# CPU.net
KiCad netlist of a schematic drawn in Altium Designer
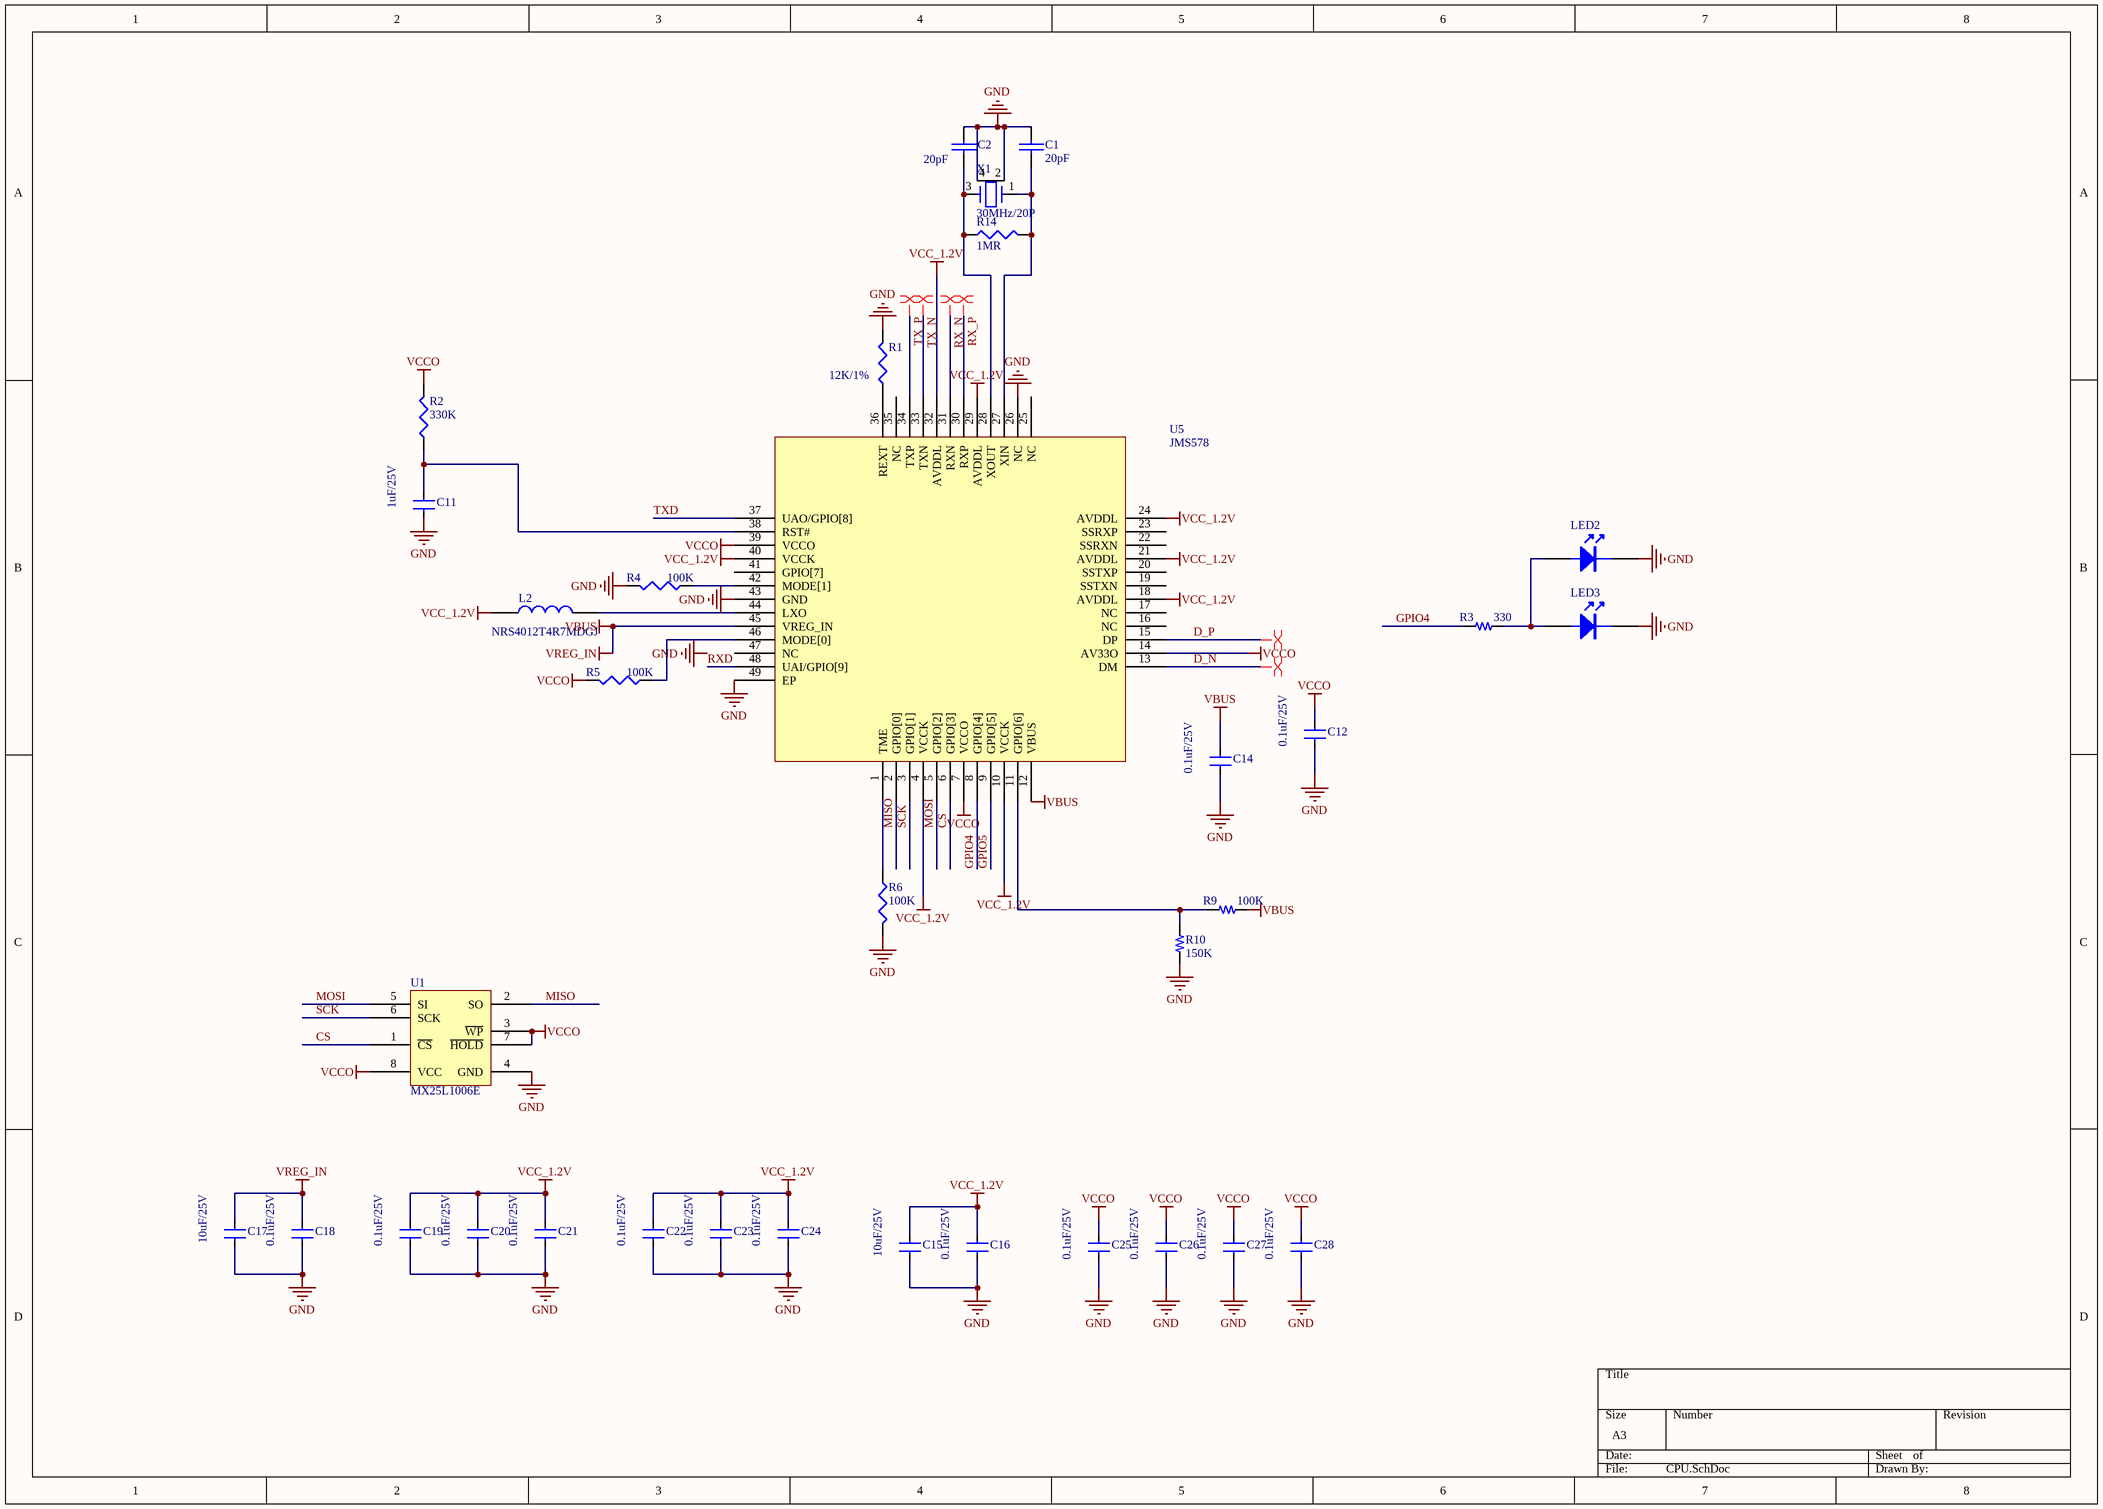
[diagram p0: CPU.SchDoc]

(export (version "E")
  (design (tool "Eeschema 10.0.6"))
  (components
    (comp (ref "C1")
      (value "20pF")
      (footprint "0603c")
      (description "Capacitor")
      (libsource (lib "SM") (part "CAP"))
    )
    (comp (ref "C2")
      (value "20pF")
      (footprint "0603C")
      (description "Capacitor")
      (libsource (lib "SM") (part "CAP"))
    )
    (comp (ref "C11")
      (value "1uF/25V")
      (footprint "0603C")
      (description "CCX85-103")
      (libsource (lib "无极性电容") (part "0.01UF"))
    )
    (comp (ref "C12")
      (value "0.1uF/25V")
      (footprint "0603C")
      (description "CCX85-103")
      (libsource (lib "无极性电容") (part "0.01UF"))
    )
    (comp (ref "C14")
      (value "0.1uF/25V")
      (footprint "0603C")
      (description "CCX85-103")
      (libsource (lib "无极性电容") (part "0.01UF"))
    )
    (comp (ref "C15")
      (value "10uF/25V")
      (footprint "0603C")
      (description "CCX85-103")
      (libsource (lib "无极性电容") (part "0.01UF"))
    )
    (comp (ref "C16")
      (value "0.1uF/25V")
      (footprint "0603C")
      (description "CCX85-103")
      (libsource (lib "无极性电容") (part "0.01UF"))
    )
    (comp (ref "C17")
      (value "10uF/25V")
      (footprint "0603C")
      (description "CCX85-103")
      (libsource (lib "无极性电容") (part "0.01UF"))
    )
    (comp (ref "C18")
      (value "0.1uF/25V")
      (footprint "0603C")
      (description "CCX85-103")
      (libsource (lib "无极性电容") (part "0.01UF"))
    )
    (comp (ref "C19")
      (value "0.1uF/25V")
      (footprint "0603C")
      (description "CCX85-103")
      (libsource (lib "无极性电容") (part "0.01UF"))
    )
    (comp (ref "C20")
      (value "0.1uF/25V")
      (footprint "0603C")
      (description "CCX85-103")
      (libsource (lib "无极性电容") (part "0.01UF"))
    )
    (comp (ref "C21")
      (value "0.1uF/25V")
      (footprint "0603C")
      (description "CCX85-103")
      (libsource (lib "无极性电容") (part "0.01UF"))
    )
    (comp (ref "C22")
      (value "0.1uF/25V")
      (footprint "0603C")
      (description "CCX85-103")
      (libsource (lib "无极性电容") (part "0.01UF"))
    )
    (comp (ref "C23")
      (value "0.1uF/25V")
      (footprint "0603C")
      (description "CCX85-103")
      (libsource (lib "无极性电容") (part "0.01UF"))
    )
    (comp (ref "C24")
      (value "0.1uF/25V")
      (footprint "0603C")
      (description "CCX85-103")
      (libsource (lib "无极性电容") (part "0.01UF"))
    )
    (comp (ref "C25")
      (value "0.1uF/25V")
      (footprint "0603C")
      (description "CCX85-103")
      (libsource (lib "无极性电容") (part "0.01UF"))
    )
    (comp (ref "C26")
      (value "0.1uF/25V")
      (footprint "0603C")
      (description "CCX85-103")
      (libsource (lib "无极性电容") (part "0.01UF"))
    )
    (comp (ref "C27")
      (value "0.1uF/25V")
      (footprint "0603C")
      (description "CCX85-103")
      (libsource (lib "无极性电容") (part "0.01UF"))
    )
    (comp (ref "C28")
      (value "0.1uF/25V")
      (footprint "0603C")
      (description "CCX85-103")
      (libsource (lib "无极性电容") (part "0.01UF"))
    )
    (comp (ref "L2")
      (value "NRS4012T4R7MDGJ")
      (footprint "NRS4012T4R7MDGJ")
      (libsource (lib "*") (part "INDUCTOR"))
    )
    (comp (ref "LED2") (value "~") (footprint "0603LED") (libsource (lib "*") (part "LED")))
    (comp (ref "LED3") (value "~") (footprint "0603LED") (libsource (lib "*") (part "LED")))
    (comp (ref "R1")
      (value "12K/1%")
      (footprint "0603R")
      (description "Resistor")
      (fields (field (name "PUBLISHER") "Altium Limited"))
      (libsource (lib "SM") (part "Res3"))
    )
    (comp (ref "R2")
      (value "330K")
      (footprint "0603R")
      (description "Resistor")
      (fields (field (name "PUBLISHER") "Altium Limited"))
      (libsource (lib "SM") (part "Res3"))
    )
    (comp (ref "R3") (value "330") (footprint "0603R") (description "R") (libsource (lib "JRJ_1") (part "R")))
    (comp (ref "R4")
      (value "100K")
      (footprint "0603R")
      (description "Resistor")
      (fields (field (name "PUBLISHER") "Altium Limited"))
      (libsource (lib "SM") (part "Res3"))
    )
    (comp (ref "R5")
      (value "100K")
      (footprint "0603R")
      (description "Resistor")
      (fields (field (name "PUBLISHER") "Altium Limited"))
      (libsource (lib "SM") (part "Res3"))
    )
    (comp (ref "R6")
      (value "100K")
      (footprint "0603R")
      (description "Resistor")
      (fields (field (name "PUBLISHER") "Altium Limited"))
      (libsource (lib "SM") (part "Res3"))
    )
    (comp (ref "R9")
      (value "100K")
      (footprint "0603R")
      (description "R")
      (libsource (lib "JRJ_1") (part "R"))
    )
    (comp (ref "R10")
      (value "150K")
      (footprint "0603R")
      (description "R")
      (libsource (lib "JRJ_1") (part "R"))
    )
    (comp (ref "R14")
      (value "1MR")
      (footprint "0603R")
      (description "Resistor")
      (fields (field (name "PUBLISHER") "Altium Limited"))
      (libsource (lib "SM") (part "Res3"))
    )
    (comp (ref "U1")
      (value "MX25L1006E")
      (footprint "SO-8")
      (libsource (lib "Schlib_20110825") (part "M25P40-VMN6"))
    )
    (comp (ref "U5") (value "JMS578") (footprint "QFN400P600-8N") (libsource (lib "stm32") (part "JMS578")))
    (comp (ref "X1")
      (value "30MHz/20P")
      (footprint "XTAL4TN_3225")
      (libsource (lib "JRJ") (part "CRYSTAL_2"))
    )
  )
  (nets
    (net (code "1") (name "/CS") (class "Default")
      (node (ref "U1") (pin "1") (pinfunction "~{CS}_1") (pintype "passive"))
      (node (ref "U5") (pin "6") (pinfunction "GPIO[3]_6") (pintype "passive"))
    )
    (net (code "2") (name "/D_N") (class "Default")
      (node (ref "U5") (pin "13") (pinfunction "DM_13") (pintype "passive"))
    )
    (net (code "3") (name "/D_P") (class "Default")
      (node (ref "U5") (pin "15") (pinfunction "DP_15") (pintype "passive"))
    )
    (net (code "4") (name "/GPIO4") (class "Default")
      (node (ref "R3") (pin "1") (pintype "passive"))
      (node (ref "U5") (pin "8") (pinfunction "GPIO[4]_8") (pintype "passive"))
    )
    (net (code "5") (name "/GPIO5") (class "Default")
      (node (ref "U5") (pin "9") (pinfunction "GPIO[5]_9") (pintype "passive"))
    )
    (net (code "6") (name "/MISO") (class "Default")
      (node (ref "U1") (pin "2") (pinfunction "SO_2") (pintype "passive"))
      (node (ref "U5") (pin "2") (pinfunction "GPIO[0]_2") (pintype "passive"))
    )
    (net (code "7") (name "/MOSI") (class "Default")
      (node (ref "U1") (pin "5") (pinfunction "SI_5") (pintype "passive"))
      (node (ref "U5") (pin "5") (pinfunction "GPIO[2]_5") (pintype "passive"))
    )
    (net (code "8") (name "/RXD") (class "Default")
      (node (ref "U5") (pin "48") (pinfunction "UAI/GPIO[9]_48") (pintype "passive"))
    )
    (net (code "9") (name "/RX_N") (class "Default")
      (node (ref "U5") (pin "31") (pinfunction "RXN_31") (pintype "passive"))
    )
    (net (code "10") (name "/RX_P") (class "Default")
      (node (ref "U5") (pin "30") (pinfunction "RXP_30") (pintype "passive"))
    )
    (net (code "11") (name "/SCK") (class "Default")
      (node (ref "U1") (pin "6") (pinfunction "SCK_6") (pintype "passive"))
      (node (ref "U5") (pin "3") (pinfunction "GPIO[1]_3") (pintype "passive"))
    )
    (net (code "12") (name "/TXD") (class "Default")
      (node (ref "U5") (pin "37") (pinfunction "UAO/GPIO[8]_37") (pintype "passive"))
    )
    (net (code "13") (name "/TX_N") (class "Default")
      (node (ref "U5") (pin "33") (pinfunction "TXN_33") (pintype "passive"))
    )
    (net (code "14") (name "/TX_P") (class "Default")
      (node (ref "U5") (pin "34") (pinfunction "TXP_34") (pintype "passive"))
    )
    (net (code "15") (name "GND") (class "Default")
      (node (ref "C1") (pin "1") (pinfunction "1_1") (pintype "passive"))
      (node (ref "C11") (pin "2") (pinfunction "2_2") (pintype "passive"))
      (node (ref "C12") (pin "2") (pinfunction "2_2") (pintype "passive"))
      (node (ref "C14") (pin "2") (pinfunction "2_2") (pintype "passive"))
      (node (ref "C15") (pin "2") (pinfunction "2_2") (pintype "passive"))
      (node (ref "C16") (pin "2") (pinfunction "2_2") (pintype "passive"))
      (node (ref "C17") (pin "2") (pinfunction "2_2") (pintype "passive"))
      (node (ref "C18") (pin "2") (pinfunction "2_2") (pintype "passive"))
      (node (ref "C19") (pin "2") (pinfunction "2_2") (pintype "passive"))
      (node (ref "C2") (pin "1") (pinfunction "1_1") (pintype "passive"))
      (node (ref "C20") (pin "2") (pinfunction "2_2") (pintype "passive"))
      (node (ref "C21") (pin "2") (pinfunction "2_2") (pintype "passive"))
      (node (ref "C22") (pin "2") (pinfunction "2_2") (pintype "passive"))
      (node (ref "C23") (pin "2") (pinfunction "2_2") (pintype "passive"))
      (node (ref "C24") (pin "2") (pinfunction "2_2") (pintype "passive"))
      (node (ref "C25") (pin "2") (pinfunction "2_2") (pintype "passive"))
      (node (ref "C26") (pin "2") (pinfunction "2_2") (pintype "passive"))
      (node (ref "C27") (pin "2") (pinfunction "2_2") (pintype "passive"))
      (node (ref "C28") (pin "2") (pinfunction "2_2") (pintype "passive"))
      (node (ref "LED2") (pin "2") (pinfunction "2_2") (pintype "passive"))
      (node (ref "LED3") (pin "2") (pinfunction "2_2") (pintype "passive"))
      (node (ref "R1") (pin "2") (pinfunction "2_2") (pintype "passive"))
      (node (ref "R10") (pin "1") (pintype "passive"))
      (node (ref "R4") (pin "2") (pinfunction "2_2") (pintype "passive"))
      (node (ref "R6") (pin "2") (pinfunction "2_2") (pintype "passive"))
      (node (ref "U1") (pin "4") (pinfunction "GND_4") (pintype "passive"))
      (node (ref "U5") (pin "26") (pinfunction "NC_26") (pintype "passive"))
      (node (ref "U5") (pin "43") (pinfunction "GND_43") (pintype "passive"))
      (node (ref "U5") (pin "49") (pinfunction "EP_49") (pintype "passive"))
      (node (ref "X1") (pin "2") (pinfunction "GND_2") (pintype "passive"))
      (node (ref "X1") (pin "4") (pinfunction "GND_4") (pintype "passive"))
    )
    (net (code "16") (name "Net-(LED2-Pad1)") (class "Default")
      (node (ref "LED2") (pin "1") (pinfunction "1_1") (pintype "passive"))
      (node (ref "LED3") (pin "1") (pinfunction "1_1") (pintype "passive"))
      (node (ref "R3") (pin "2") (pintype "passive"))
    )
    (net (code "17") (name "Net-(U5-GPIO[6])") (class "Default")
      (node (ref "R10") (pin "2") (pintype "passive"))
      (node (ref "R9") (pin "1") (pintype "passive"))
      (node (ref "U5") (pin "11") (pinfunction "GPIO[6]_11") (pintype "passive"))
    )
    (net (code "18") (name "Net-(U5-LXO)") (class "Default")
      (node (ref "L2") (pin "2") (pinfunction "2_2") (pintype "passive"))
      (node (ref "U5") (pin "44") (pinfunction "LXO_44") (pintype "passive"))
    )
    (net (code "19") (name "Net-(U5-MODE[0])") (class "Default")
      (node (ref "R5") (pin "1") (pinfunction "1_1") (pintype "passive"))
      (node (ref "U5") (pin "46") (pinfunction "MODE[0]_46") (pintype "passive"))
    )
    (net (code "20") (name "Net-(U5-MODE[1])") (class "Default")
      (node (ref "R4") (pin "1") (pinfunction "1_1") (pintype "passive"))
      (node (ref "U5") (pin "42") (pinfunction "MODE[1]_42") (pintype "passive"))
    )
    (net (code "21") (name "Net-(U5-REXT)") (class "Default")
      (node (ref "R1") (pin "1") (pinfunction "1_1") (pintype "passive"))
      (node (ref "U5") (pin "36") (pinfunction "REXT_36") (pintype "passive"))
    )
    (net (code "22") (name "Net-(U5-RST#)") (class "Default")
      (node (ref "C11") (pin "1") (pinfunction "1_1") (pintype "passive"))
      (node (ref "R2") (pin "1") (pinfunction "1_1") (pintype "passive"))
      (node (ref "U5") (pin "38") (pinfunction "RST#_38") (pintype "passive"))
    )
    (net (code "23") (name "Net-(U5-TME)") (class "Default")
      (node (ref "R6") (pin "1") (pinfunction "1_1") (pintype "passive"))
      (node (ref "U5") (pin "1") (pinfunction "TME_1") (pintype "passive"))
    )
    (net (code "24") (name "Net-(U5-XIN)") (class "Default")
      (node (ref "C1") (pin "2") (pinfunction "2_2") (pintype "passive"))
      (node (ref "R14") (pin "2") (pinfunction "2_2") (pintype "passive"))
      (node (ref "U5") (pin "27") (pinfunction "XIN_27") (pintype "passive"))
      (node (ref "X1") (pin "1") (pinfunction "X1_1") (pintype "passive"))
    )
    (net (code "25") (name "Net-(U5-XOUT)") (class "Default")
      (node (ref "C2") (pin "2") (pinfunction "2_2") (pintype "passive"))
      (node (ref "R14") (pin "1") (pinfunction "1_1") (pintype "passive"))
      (node (ref "U5") (pin "28") (pinfunction "XOUT_28") (pintype "passive"))
      (node (ref "X1") (pin "3") (pinfunction "X2_3") (pintype "passive"))
    )
    (net (code "26") (name "VBUS") (class "Default")
      (node (ref "C14") (pin "1") (pinfunction "1_1") (pintype "passive"))
      (node (ref "C17") (pin "1") (pinfunction "1_1") (pintype "passive"))
      (node (ref "C18") (pin "1") (pinfunction "1_1") (pintype "passive"))
      (node (ref "R9") (pin "2") (pintype "passive"))
      (node (ref "U5") (pin "12") (pinfunction "VBUS_12") (pintype "passive"))
      (node (ref "U5") (pin "45") (pinfunction "VREG_IN_45") (pintype "passive"))
    )
    (net (code "27") (name "VCCO") (class "Default")
      (node (ref "C12") (pin "1") (pinfunction "1_1") (pintype "passive"))
      (node (ref "C25") (pin "1") (pinfunction "1_1") (pintype "passive"))
      (node (ref "C26") (pin "1") (pinfunction "1_1") (pintype "passive"))
      (node (ref "C27") (pin "1") (pinfunction "1_1") (pintype "passive"))
      (node (ref "C28") (pin "1") (pinfunction "1_1") (pintype "passive"))
      (node (ref "R2") (pin "2") (pinfunction "2_2") (pintype "passive"))
      (node (ref "R5") (pin "2") (pinfunction "2_2") (pintype "passive"))
      (node (ref "U1") (pin "3") (pinfunction "~{WP}_3") (pintype "passive"))
      (node (ref "U1") (pin "7") (pinfunction "~{HOLD}_7") (pintype "passive"))
      (node (ref "U1") (pin "8") (pinfunction "VCC_8") (pintype "passive"))
      (node (ref "U5") (pin "14") (pinfunction "AV33O_14") (pintype "passive"))
      (node (ref "U5") (pin "39") (pinfunction "VCCO_39") (pintype "passive"))
      (node (ref "U5") (pin "7") (pinfunction "VCCO_7") (pintype "passive"))
    )
    (net (code "28") (name "VCC_1.2V") (class "Default")
      (node (ref "C15") (pin "1") (pinfunction "1_1") (pintype "passive"))
      (node (ref "C16") (pin "1") (pinfunction "1_1") (pintype "passive"))
      (node (ref "C19") (pin "1") (pinfunction "1_1") (pintype "passive"))
      (node (ref "C20") (pin "1") (pinfunction "1_1") (pintype "passive"))
      (node (ref "C21") (pin "1") (pinfunction "1_1") (pintype "passive"))
      (node (ref "C22") (pin "1") (pinfunction "1_1") (pintype "passive"))
      (node (ref "C23") (pin "1") (pinfunction "1_1") (pintype "passive"))
      (node (ref "C24") (pin "1") (pinfunction "1_1") (pintype "passive"))
      (node (ref "L2") (pin "1") (pinfunction "1_1") (pintype "passive"))
      (node (ref "U5") (pin "10") (pinfunction "VCCK_10") (pintype "passive"))
      (node (ref "U5") (pin "18") (pinfunction "AVDDL_18") (pintype "passive"))
      (node (ref "U5") (pin "21") (pinfunction "AVDDL_21") (pintype "passive"))
      (node (ref "U5") (pin "24") (pinfunction "AVDDL_24") (pintype "passive"))
      (node (ref "U5") (pin "29") (pinfunction "AVDDL_29") (pintype "passive"))
      (node (ref "U5") (pin "32") (pinfunction "AVDDL_32") (pintype "passive"))
      (node (ref "U5") (pin "4") (pinfunction "VCCK_4") (pintype "passive"))
      (node (ref "U5") (pin "40") (pinfunction "VCCK_40") (pintype "passive"))
    )
    (net (code "29") (name "unconnected-(U5-GPIO[7]-Pad41)") (class "Default")
      (node (ref "U5") (pin "41") (pinfunction "GPIO[7]_41") (pintype "passive"))
    )
    (net (code "30") (name "unconnected-(U5-NC-Pad16)") (class "Default")
      (node (ref "U5") (pin "16") (pinfunction "NC_16") (pintype "passive"))
    )
    (net (code "31") (name "unconnected-(U5-NC-Pad17)") (class "Default")
      (node (ref "U5") (pin "17") (pinfunction "NC_17") (pintype "passive"))
    )
    (net (code "32") (name "unconnected-(U5-NC-Pad25)") (class "Default")
      (node (ref "U5") (pin "25") (pinfunction "NC_25") (pintype "passive"))
    )
    (net (code "33") (name "unconnected-(U5-NC-Pad35)") (class "Default")
      (node (ref "U5") (pin "35") (pinfunction "NC_35") (pintype "passive"))
    )
    (net (code "34") (name "unconnected-(U5-NC-Pad47)") (class "Default")
      (node (ref "U5") (pin "47") (pinfunction "NC_47") (pintype "passive"))
    )
    (net (code "35") (name "unconnected-(U5-SSRXN-Pad22)") (class "Default")
      (node (ref "U5") (pin "22") (pinfunction "SSRXN_22") (pintype "passive"))
    )
    (net (code "36") (name "unconnected-(U5-SSRXP-Pad23)") (class "Default")
      (node (ref "U5") (pin "23") (pinfunction "SSRXP_23") (pintype "passive"))
    )
    (net (code "37") (name "unconnected-(U5-SSTXN-Pad19)") (class "Default")
      (node (ref "U5") (pin "19") (pinfunction "SSTXN_19") (pintype "passive"))
    )
    (net (code "38") (name "unconnected-(U5-SSTXP-Pad20)") (class "Default")
      (node (ref "U5") (pin "20") (pinfunction "SSTXP_20") (pintype "passive"))
    )
  )
)
